# Power_Supply_Rev_G.net
KiCad netlist of a schematic drawn in EAGLE
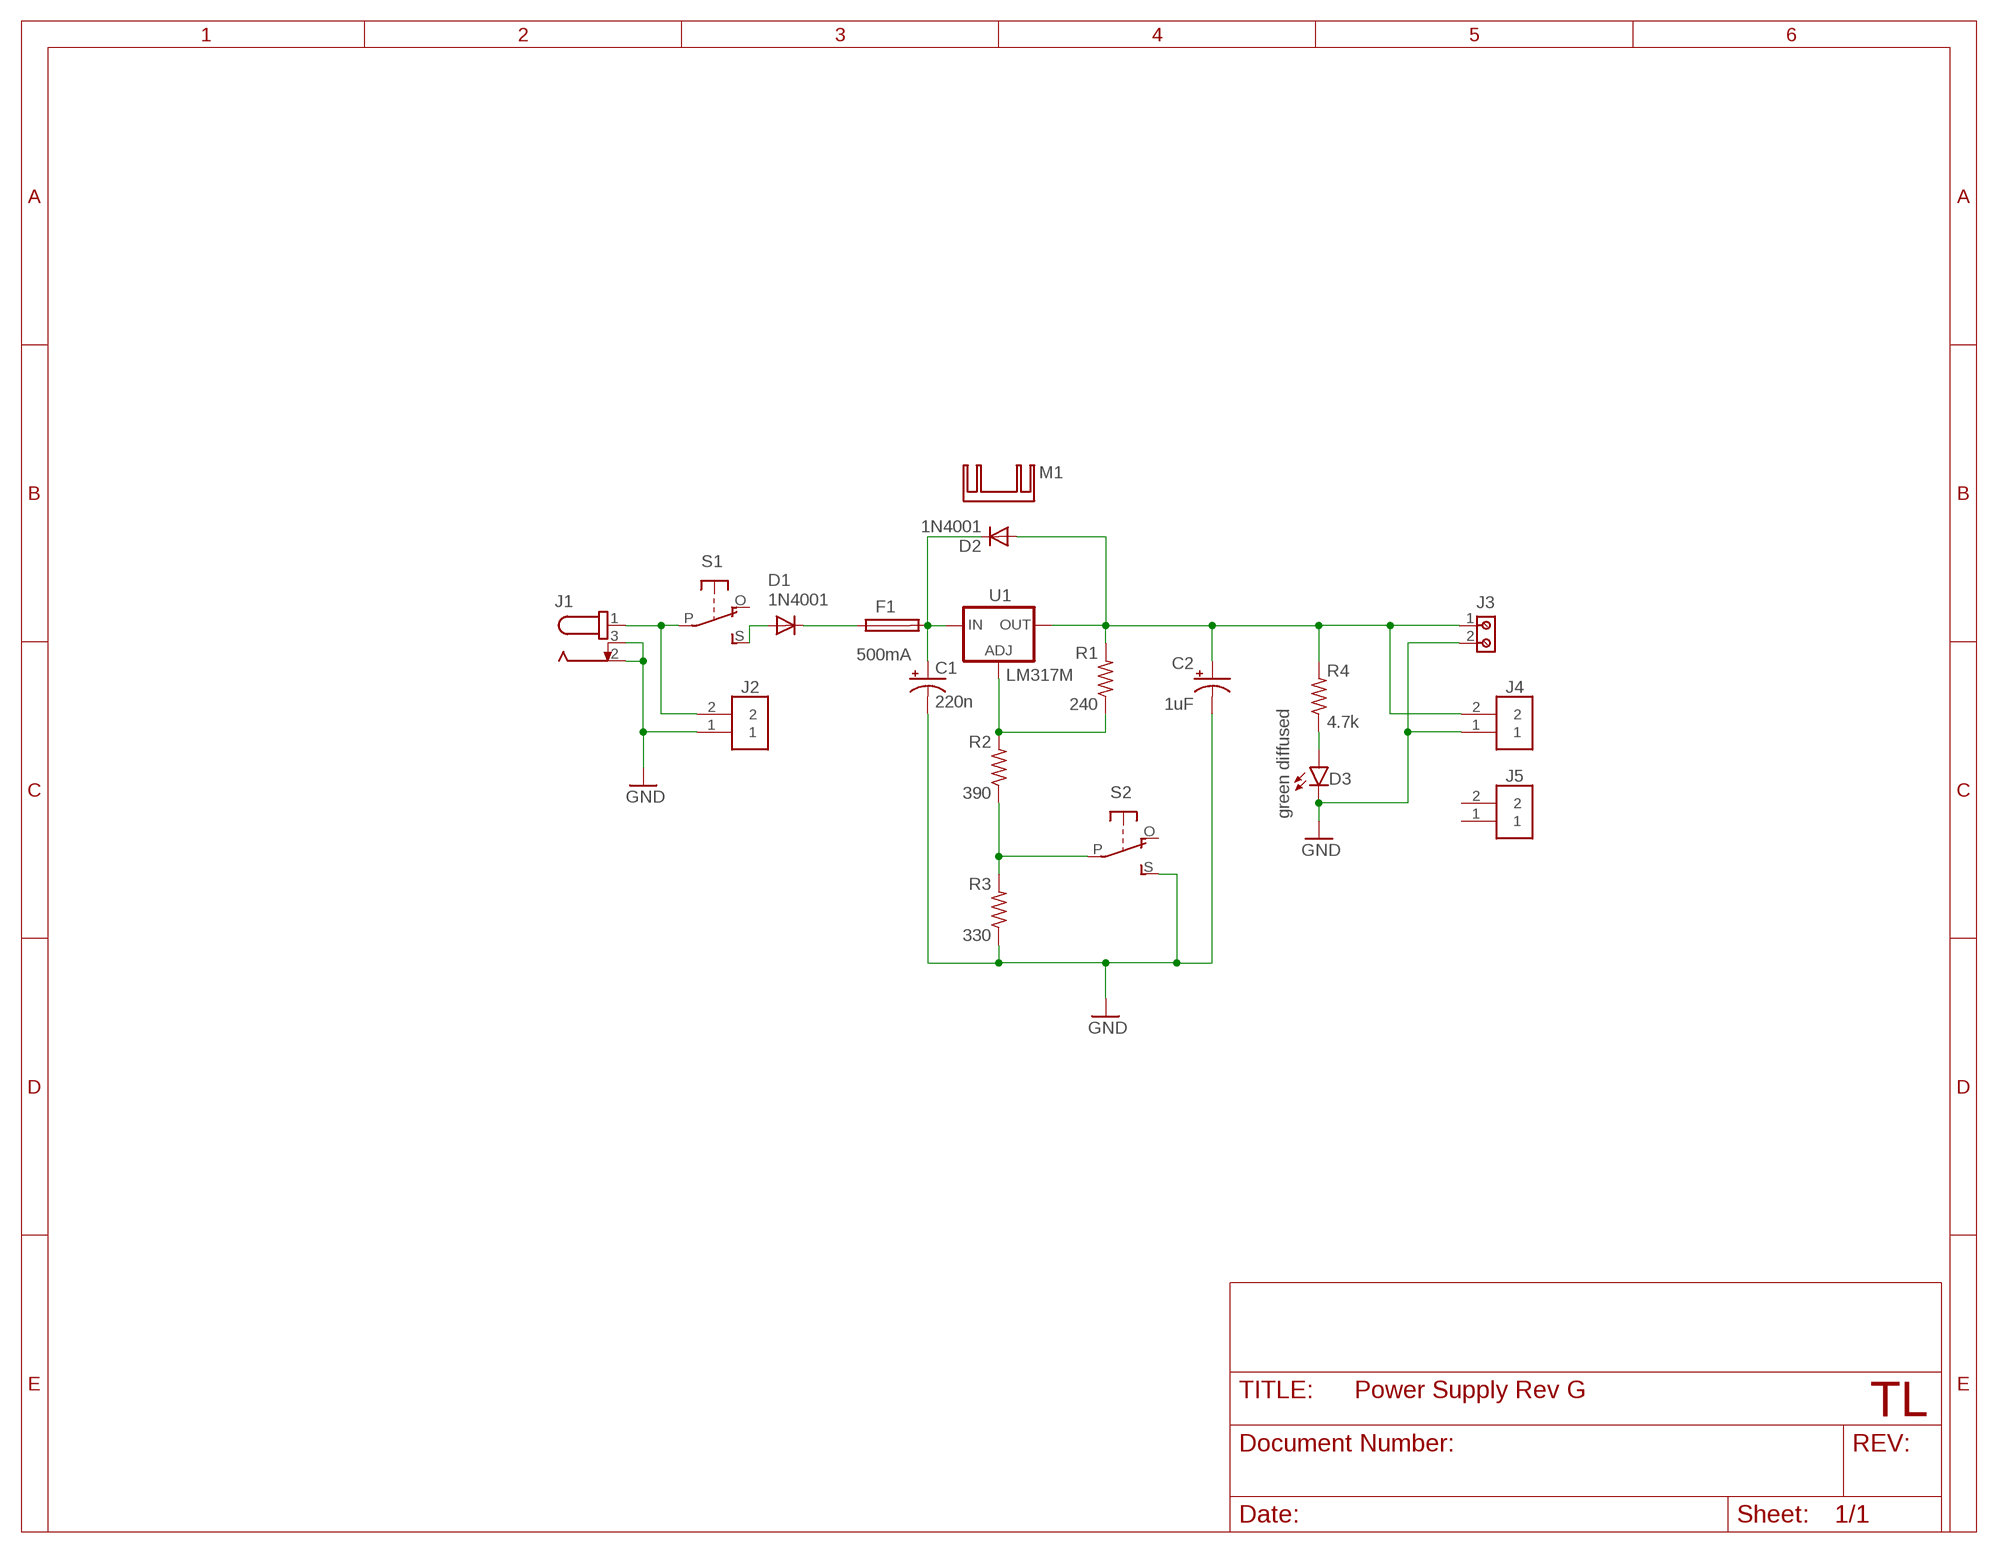
[diagram p0: schematic, sheet 1]

(export (version "E")
  (design (tool "Eeschema 10.0.6"))
  (components
    (comp (ref "C1")
      (value "220n")
      (footprint "eagle-import:E2-4")
      (libsource (lib "eagle-import") (part "E-CAPACITOR2-4"))
    )
    (comp (ref "C2")
      (value "1uF")
      (footprint "eagle-import:E2-4")
      (libsource (lib "eagle-import") (part "E-CAPACITOR2-4"))
    )
    (comp (ref "D1")
      (value "1N4001")
      (footprint "eagle-import:DO41-10")
      (libsource (lib "eagle-import") (part "1N4000"))
    )
    (comp (ref "D2")
      (value "1N4001")
      (footprint "eagle-import:DO41-10")
      (libsource (lib "eagle-import") (part "1N4000"))
    )
    (comp (ref "D3")
      (value "green diffused")
      (footprint "eagle-import:LED5MM")
      (libsource (lib "eagle-import") (part "LED"))
    )
    (comp (ref "F1")
      (value "500mA")
      (footprint "eagle-import:PTC-FUSE")
      (libsource (lib "eagle-import") (part "PTC-FUSE"))
    )
    (comp (ref "J1")
      (value "694106301002")
      (footprint "eagle-import:694106301002")
      (fields
        (field (name "DIGIKEY_PART_NUMBER") "732-5930-ND")
        (field (name "MANUFACTURER") "Wurth Electronics Inc.")
        (field (name "CREATED_BY") "PCBLayout.com")
      )
      (libsource (lib "eagle-import") (part "694106301002"))
    )
    (comp (ref "J2")
      (value "61300211121")
      (footprint "eagle-import:61300211121")
      (fields
        (field (name "DIGI_KEY_PART_NUMBER") "732-5315-ND")
        (field (name "MANUFACTURER") "Wurth Electronics Inc.")
        (field (name "CREATED_BY") "PCBLayout.com")
      )
      (libsource (lib "eagle-import") (part "61300211121"))
    )
    (comp (ref "J3")
      (value "691214110002")
      (footprint "eagle-import:691214110002")
      (libsource (lib "eagle-import") (part "691214110002"))
    )
    (comp (ref "J4")
      (value "61300211121")
      (footprint "eagle-import:61300211121")
      (fields
        (field (name "DIGI_KEY_PART_NUMBER") "732-5315-ND")
        (field (name "MANUFACTURER") "Wurth Electronics Inc.")
        (field (name "CREATED_BY") "PCBLayout.com")
      )
      (libsource (lib "eagle-import") (part "61300211121"))
    )
    (comp (ref "J5")
      (value "61300211121")
      (footprint "eagle-import:61300211121")
      (fields
        (field (name "DIGI_KEY_PART_NUMBER") "732-5315-ND")
        (field (name "MANUFACTURER") "Wurth Electronics Inc.")
        (field (name "CREATED_BY") "PCBLayout.com")
      )
      (libsource (lib "eagle-import") (part "61300211121"))
    )
    (comp (ref "M1")
      (value "TO220-HEATSINK")
      (footprint "eagle-import:D03S")
      (libsource (lib "eagle-import") (part "TO220-HEATSINK"))
    )
    (comp (ref "R1")
      (value "240")
      (footprint "eagle-import:0207_10")
      (libsource (lib "eagle-import") (part "RESISTOR"))
    )
    (comp (ref "R2")
      (value "390")
      (footprint "eagle-import:0207_10")
      (libsource (lib "eagle-import") (part "RESISTOR"))
    )
    (comp (ref "R3")
      (value "330")
      (footprint "eagle-import:0207_10")
      (libsource (lib "eagle-import") (part "RESISTOR"))
    )
    (comp (ref "R4")
      (value "4.7k")
      (footprint "eagle-import:0207_10")
      (libsource (lib "eagle-import") (part "RESISTOR"))
    )
    (comp (ref "S1")
      (value "SLIDE-SWITCHSIDE")
      (footprint "eagle-import:EG1270-90")
      (libsource (lib "eagle-import") (part "SLIDE-SWITCHSIDE"))
    )
    (comp (ref "S2")
      (value "SLIDE-SWITCHSIDE")
      (footprint "eagle-import:EG1270-90")
      (libsource (lib "eagle-import") (part "SLIDE-SWITCHSIDE"))
    )
    (comp (ref "U1")
      (value "LM317")
      (footprint "eagle-import:317TS")
      (fields (field (name "PARTNUMBER") "LM317M"))
      (libsource (lib "eagle-import") (part "LM317"))
    )
  )
  (nets
    (net (code "1") (name "GND") (class "Default")
      (node (ref "C1") (pin "-") (pinfunction "-_-") (pintype "passive"))
      (node (ref "C2") (pin "-") (pinfunction "-_-") (pintype "passive"))
      (node (ref "D3") (pin "K") (pinfunction "C_K") (pintype "passive"))
      (node (ref "J1") (pin "2") (pinfunction "2_2") (pintype "passive"))
      (node (ref "J1") (pin "3") (pinfunction "3_3") (pintype "passive"))
      (node (ref "J2") (pin "1") (pinfunction "1_1") (pintype "passive"))
      (node (ref "J3") (pin "2") (pinfunction "2_2") (pintype "passive"))
      (node (ref "J4") (pin "1") (pinfunction "1_1") (pintype "passive"))
      (node (ref "R3") (pin "1") (pinfunction "1_1") (pintype "passive"))
      (node (ref "S2") (pin "S") (pinfunction "S_S") (pintype "passive"))
    )
    (net (code "2") (name "Net-(D1-PadA)") (class "Default")
      (node (ref "D1") (pin "A") (pinfunction "A_A") (pintype "passive"))
      (node (ref "S1") (pin "S") (pinfunction "S_S") (pintype "passive"))
    )
    (net (code "3") (name "Net-(D1-PadC)") (class "Default")
      (node (ref "D1") (pin "C") (pinfunction "C_C") (pintype "passive"))
      (node (ref "F1") (pin "1") (pinfunction "1_1") (pintype "passive"))
    )
    (net (code "4") (name "Net-(D3-PadA)") (class "Default")
      (node (ref "D3") (pin "A") (pinfunction "A_A") (pintype "passive"))
      (node (ref "R4") (pin "1") (pinfunction "1_1") (pintype "passive"))
    )
    (net (code "5") (name "Net-(J1-Pad1)") (class "Default")
      (node (ref "J1") (pin "1") (pinfunction "1_1") (pintype "passive"))
      (node (ref "J2") (pin "2") (pinfunction "2_2") (pintype "passive"))
      (node (ref "S1") (pin "P") (pinfunction "P_P") (pintype "passive"))
    )
    (net (code "6") (name "Net-(R2-Pad1)") (class "Default")
      (node (ref "R2") (pin "1") (pinfunction "1_1") (pintype "passive"))
      (node (ref "R3") (pin "2") (pinfunction "2_2") (pintype "passive"))
      (node (ref "S2") (pin "P") (pinfunction "P_P") (pintype "passive"))
    )
    (net (code "7") (name "Net-(U1-ADJ)") (class "Default")
      (node (ref "R1") (pin "1") (pinfunction "1_1") (pintype "passive"))
      (node (ref "R2") (pin "2") (pinfunction "2_2") (pintype "passive"))
      (node (ref "U1") (pin "1") (pinfunction "ADJ_1") (pintype "input"))
    )
    (net (code "8") (name "Net-(U1-IN)") (class "Default")
      (node (ref "C1") (pin "+") (pinfunction "+_+") (pintype "passive"))
      (node (ref "D2") (pin "C") (pinfunction "C_C") (pintype "passive"))
      (node (ref "F1") (pin "2") (pinfunction "2_2") (pintype "passive"))
      (node (ref "U1") (pin "3") (pinfunction "IN_3") (pintype "input"))
    )
    (net (code "9") (name "Net-(U1-OUT)") (class "Default")
      (node (ref "C2") (pin "+") (pinfunction "+_+") (pintype "passive"))
      (node (ref "D2") (pin "A") (pinfunction "A_A") (pintype "passive"))
      (node (ref "J3") (pin "1") (pinfunction "1_1") (pintype "passive"))
      (node (ref "J4") (pin "2") (pinfunction "2_2") (pintype "passive"))
      (node (ref "R1") (pin "2") (pinfunction "2_2") (pintype "passive"))
      (node (ref "R4") (pin "2") (pinfunction "2_2") (pintype "passive"))
      (node (ref "U1") (pin "2") (pinfunction "OUT_2") (pintype "passive"))
    )
    (net (code "10") (name "unconnected-(J5-Pad1)") (class "Default")
      (node (ref "J5") (pin "1") (pinfunction "1_1") (pintype "passive"))
    )
    (net (code "11") (name "unconnected-(J5-Pad2)") (class "Default")
      (node (ref "J5") (pin "2") (pinfunction "2_2") (pintype "passive"))
    )
    (net (code "12") (name "unconnected-(S1-PadO)") (class "Default")
      (node (ref "S1") (pin "O") (pinfunction "O_O") (pintype "passive"))
    )
    (net (code "13") (name "unconnected-(S2-PadO)") (class "Default")
      (node (ref "S2") (pin "O") (pinfunction "O_O") (pintype "passive"))
    )
  )
)
